# IrSensor.net
KiCad netlist of a schematic drawn in EAGLE
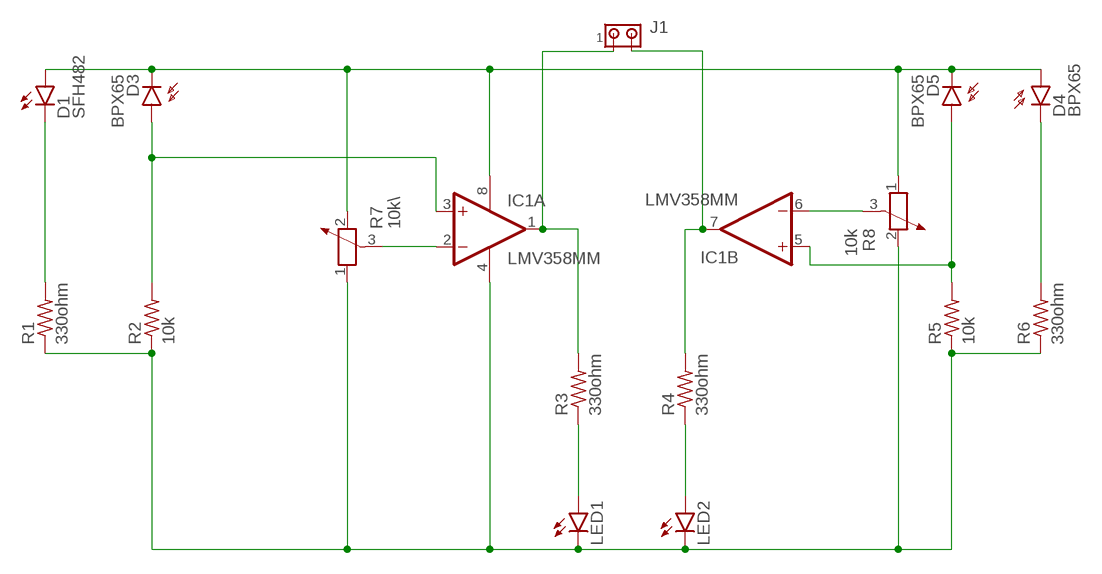
[diagram p0: schematic, sheet 1]

(export (version "E")
  (design (tool "Eeschema 10.0.6"))
  (components
    (comp (ref "D1")
      (value "SFH482")
      (footprint "eagle-import:SFH482")
      (libsource (lib "eagle-import") (part "SFH482"))
    )
    (comp (ref "D3")
      (value "BPX65")
      (footprint "eagle-import:BPX65")
      (fields (field (name "MPN") "BPX65."))
      (libsource (lib "eagle-import") (part "BPX65"))
    )
    (comp (ref "D4")
      (value "BPX65")
      (footprint "eagle-import:BPX65")
      (fields (field (name "MPN") "BPX65."))
      (libsource (lib "eagle-import") (part "BPX65"))
    )
    (comp (ref "D5")
      (value "BPX65")
      (footprint "eagle-import:BPX65")
      (fields (field (name "MPN") "BPX65."))
      (libsource (lib "eagle-import") (part "BPX65"))
    )
    (comp (ref "IC1")
      (value "LMV358MM")
      (footprint "eagle-import:MSOP08")
      (libsource (lib "eagle-import") (part "LMV358?MM"))
    )
    (comp (ref "J1")
      (value "MTA02-100")
      (footprint "eagle-import:10X02MTA")
      (libsource (lib "eagle-import") (part "MTA02-100"))
    )
    (comp (ref "LED1")
      (value "LED3MM")
      (footprint "eagle-import:LED3MM")
      (libsource (lib "eagle-import") (part "LED3MM"))
    )
    (comp (ref "LED2")
      (value "LED3MM")
      (footprint "eagle-import:LED3MM")
      (libsource (lib "eagle-import") (part "LED3MM"))
    )
    (comp (ref "R1")
      (value "330ohm")
      (footprint "eagle-import:0207_10")
      (libsource (lib "eagle-import") (part "R-US_0207/10"))
    )
    (comp (ref "R2")
      (value "10k")
      (footprint "eagle-import:0207_10")
      (libsource (lib "eagle-import") (part "R-US_0207/10"))
    )
    (comp (ref "R3")
      (value "330ohm")
      (footprint "eagle-import:0207_10")
      (libsource (lib "eagle-import") (part "R-US_0207/10"))
    )
    (comp (ref "R4")
      (value "330ohm")
      (footprint "eagle-import:0207_10")
      (libsource (lib "eagle-import") (part "R-US_0207/10"))
    )
    (comp (ref "R5")
      (value "10k")
      (footprint "eagle-import:0207_10")
      (libsource (lib "eagle-import") (part "R-US_0207/10"))
    )
    (comp (ref "R6")
      (value "330ohm")
      (footprint "eagle-import:0207_10")
      (libsource (lib "eagle-import") (part "R-US_0207/10"))
    )
    (comp (ref "R7")
      (value "10k\\")
      (footprint "eagle-import:PT-10")
      (libsource (lib "eagle-import") (part "POTENTIOMETER_PT-10"))
    )
    (comp (ref "R8")
      (value "10k")
      (footprint "eagle-import:PT-10")
      (libsource (lib "eagle-import") (part "POTENTIOMETER_PT-10"))
    )
  )
  (nets
    (net (code "1") (name "Net-(D1-C)") (class "Default")
      (node (ref "D1") (pin "K") (pinfunction "C_K") (pintype "passive"))
      (node (ref "R1") (pin "2") (pinfunction "2_2") (pintype "passive"))
    )
    (net (code "2") (name "Net-(D3-C)") (class "Default")
      (node (ref "D1") (pin "A") (pinfunction "A_A") (pintype "passive"))
      (node (ref "D3") (pin "K") (pinfunction "C_K") (pintype "passive"))
      (node (ref "D4") (pin "A") (pinfunction "A_A") (pintype "passive"))
      (node (ref "D5") (pin "K") (pinfunction "C_K") (pintype "passive"))
      (node (ref "IC1") (pin "8") (pinfunction "V+_8") (pintype "power_in"))
      (node (ref "R7") (pin "2") (pinfunction "2_2") (pintype "passive"))
      (node (ref "R8") (pin "1") (pinfunction "1_1") (pintype "passive"))
    )
    (net (code "3") (name "Net-(D4-C)") (class "Default")
      (node (ref "D4") (pin "K") (pinfunction "C_K") (pintype "passive"))
      (node (ref "R6") (pin "2") (pinfunction "2_2") (pintype "passive"))
    )
    (net (code "4") (name "Net-(IC1A-+IN)") (class "Default")
      (node (ref "D3") (pin "A") (pinfunction "A_A") (pintype "passive"))
      (node (ref "IC1") (pin "3") (pinfunction "+IN_3") (pintype "input"))
      (node (ref "R2") (pin "2") (pinfunction "2_2") (pintype "passive"))
    )
    (net (code "5") (name "Net-(IC1A--IN)") (class "Default")
      (node (ref "IC1") (pin "2") (pinfunction "-IN_2") (pintype "input"))
      (node (ref "R7") (pin "3") (pinfunction "3_3") (pintype "passive"))
    )
    (net (code "6") (name "Net-(IC1A-OUT)") (class "Default")
      (node (ref "IC1") (pin "1") (pinfunction "OUT_1") (pintype "output"))
      (node (ref "J1") (pin "1") (pinfunction "1_1") (pintype "passive"))
      (node (ref "R3") (pin "2") (pinfunction "2_2") (pintype "passive"))
    )
    (net (code "7") (name "Net-(IC1B-+IN)") (class "Default")
      (node (ref "D5") (pin "A") (pinfunction "A_A") (pintype "passive"))
      (node (ref "IC1") (pin "5") (pinfunction "+IN_5") (pintype "input"))
      (node (ref "R5") (pin "2") (pinfunction "2_2") (pintype "passive"))
    )
    (net (code "8") (name "Net-(IC1B--IN)") (class "Default")
      (node (ref "IC1") (pin "6") (pinfunction "-IN_6") (pintype "input"))
      (node (ref "R8") (pin "3") (pinfunction "3_3") (pintype "passive"))
    )
    (net (code "9") (name "Net-(IC1B-OUT)") (class "Default")
      (node (ref "IC1") (pin "7") (pinfunction "OUT_7") (pintype "output"))
      (node (ref "J1") (pin "2") (pinfunction "2_2") (pintype "passive"))
      (node (ref "R4") (pin "2") (pinfunction "2_2") (pintype "passive"))
    )
    (net (code "10") (name "Net-(IC1C-V-)") (class "Default")
      (node (ref "IC1") (pin "4") (pinfunction "V-_4") (pintype "power_in"))
      (node (ref "LED1") (pin "K") (pinfunction "C_K") (pintype "passive"))
      (node (ref "LED2") (pin "K") (pinfunction "C_K") (pintype "passive"))
      (node (ref "R1") (pin "1") (pinfunction "1_1") (pintype "passive"))
      (node (ref "R2") (pin "1") (pinfunction "1_1") (pintype "passive"))
      (node (ref "R5") (pin "1") (pinfunction "1_1") (pintype "passive"))
      (node (ref "R6") (pin "1") (pinfunction "1_1") (pintype "passive"))
      (node (ref "R7") (pin "1") (pinfunction "1_1") (pintype "passive"))
      (node (ref "R8") (pin "2") (pinfunction "2_2") (pintype "passive"))
    )
    (net (code "11") (name "Net-(LED1-PadA)") (class "Default")
      (node (ref "LED1") (pin "A") (pinfunction "A_A") (pintype "passive"))
      (node (ref "R3") (pin "1") (pinfunction "1_1") (pintype "passive"))
    )
    (net (code "12") (name "Net-(LED2-PadA)") (class "Default")
      (node (ref "LED2") (pin "A") (pinfunction "A_A") (pintype "passive"))
      (node (ref "R4") (pin "1") (pinfunction "1_1") (pintype "passive"))
    )
  )
)
